# 03_-_SDCARD.net
KiCad netlist of a schematic drawn in Altium Designer
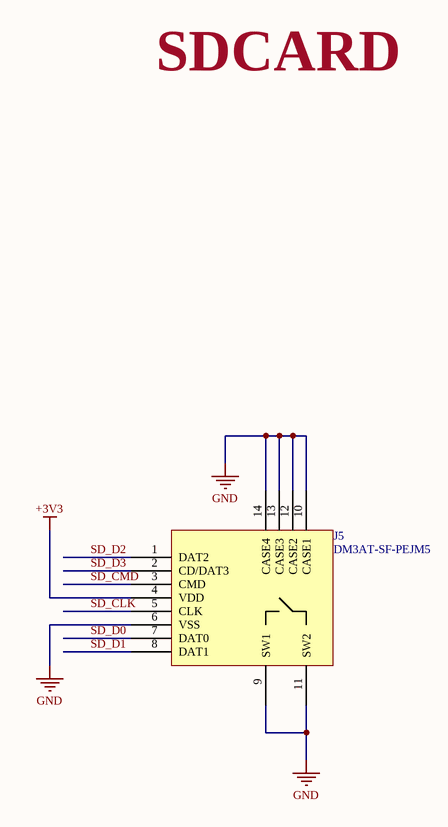
[diagram p0: [03] - SDCARD.SchDoc]

(export (version "E")
  (design (tool "Eeschema 10.0.6"))
  (components
    (comp (ref "J5")
      (value "DM3AT-SF-PEJM5")
      (footprint "uSD_DM3AT")
      (description "CONN MICRO SD R/A PUSH-PUSH SMD")
      (fields
        (field (name "MANUFACTURER") "Hirose Electric Co Ltd")
        (field (name ".CHECKED PCB") "MM")
        (field (name ".CHECKED SCH") "MM")
      )
      (libsource (lib "ECP5_V2") (part "DM3AT-SF-PEJM5"))
    )
  )
  (nets
    (net (code "1") (name "+3V3") (class "Default")
      (node (ref "J5") (pin "4") (pinfunction "VDD_4") (pintype "passive"))
    )
    (net (code "2") (name "/SD_CLK") (class "Default")
      (node (ref "J5") (pin "5") (pinfunction "CLK_5") (pintype "passive"))
    )
    (net (code "3") (name "/SD_CMD") (class "Default")
      (node (ref "J5") (pin "3") (pinfunction "CMD_3") (pintype "passive"))
    )
    (net (code "4") (name "/SD_D0") (class "Default")
      (node (ref "J5") (pin "7") (pinfunction "DAT0_7") (pintype "passive"))
    )
    (net (code "5") (name "/SD_D1") (class "Default")
      (node (ref "J5") (pin "8") (pinfunction "DAT1_8") (pintype "passive"))
    )
    (net (code "6") (name "/SD_D2") (class "Default")
      (node (ref "J5") (pin "1") (pinfunction "DAT2_1") (pintype "passive"))
    )
    (net (code "7") (name "/SD_D3") (class "Default")
      (node (ref "J5") (pin "2") (pinfunction "CD/DAT3_2") (pintype "passive"))
    )
    (net (code "8") (name "GND") (class "Default")
      (node (ref "J5") (pin "10") (pinfunction "CASE1_10") (pintype "passive"))
      (node (ref "J5") (pin "11") (pinfunction "SW2_11") (pintype "passive"))
      (node (ref "J5") (pin "12") (pinfunction "CASE2_12") (pintype "passive"))
      (node (ref "J5") (pin "13") (pinfunction "CASE3_13") (pintype "passive"))
      (node (ref "J5") (pin "14") (pinfunction "CASE4_14") (pintype "passive"))
      (node (ref "J5") (pin "6") (pinfunction "VSS_6") (pintype "passive"))
      (node (ref "J5") (pin "9") (pinfunction "SW1_9") (pintype "passive"))
    )
  )
)
